# ardBeeQueen_12-pin_lcd.net
KiCad netlist of a schematic drawn in EAGLE
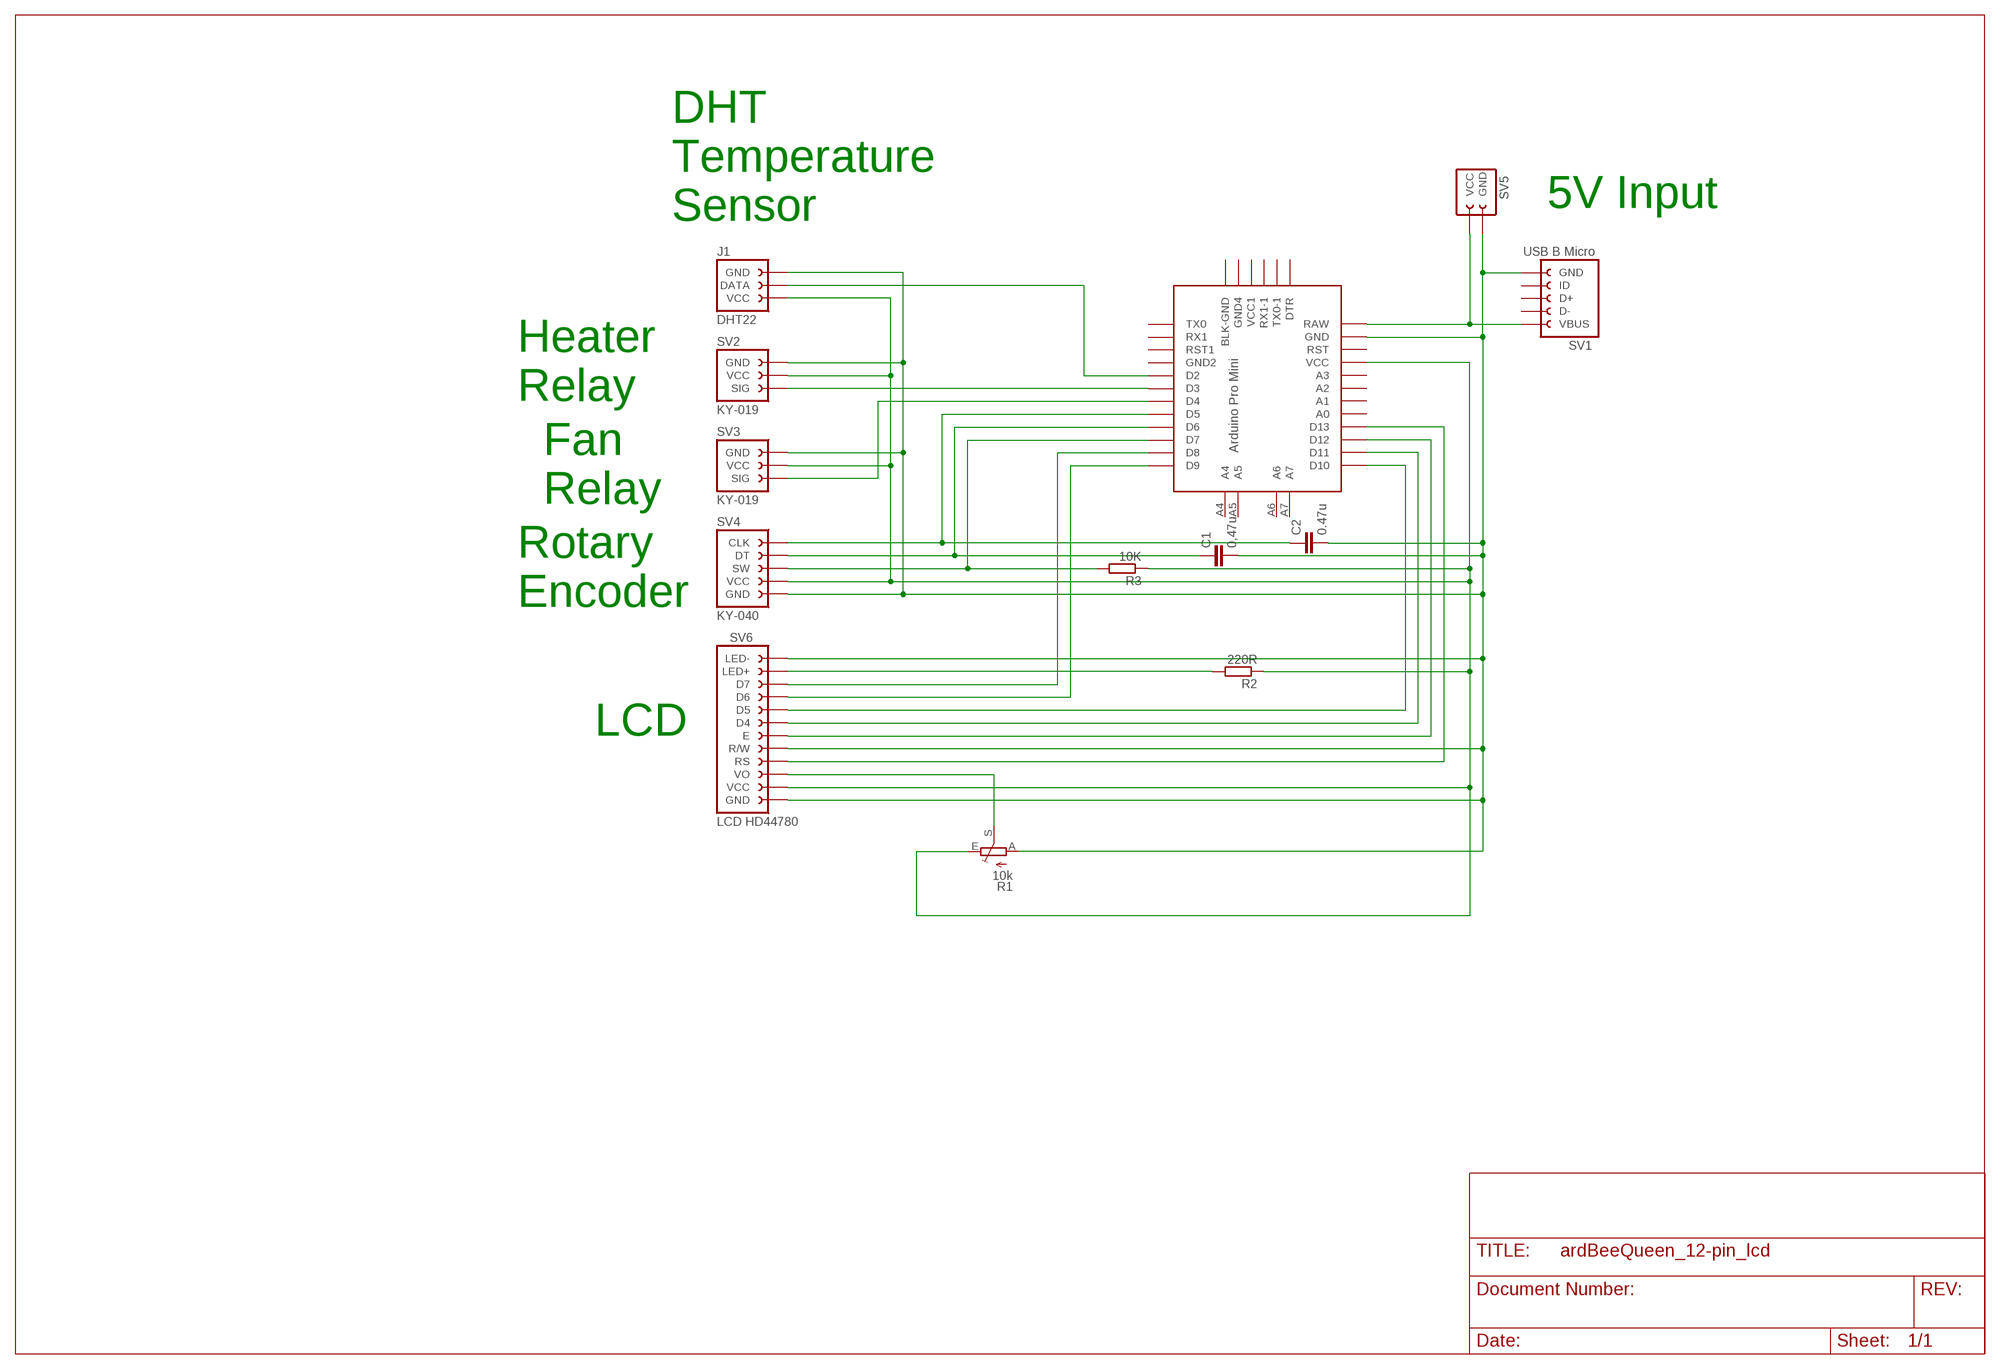
[diagram p0: schematic, sheet 1]

(export (version "E")
  (design (tool "Eeschema 10.0.6"))
  (components
    (comp (ref "C1")
      (value "0,47u")
      (footprint "eagle-import:C050-024X044")
      (libsource (lib "eagle-import") (part "C-EU050-024X044"))
    )
    (comp (ref "C2")
      (value "0.47u")
      (footprint "eagle-import:C050-024X044")
      (libsource (lib "eagle-import") (part "C-EU050-024X044"))
    )
    (comp (ref "J1")
      (value "DHT22_3-PIN_FEMALE_HEADER")
      (footprint "eagle-import:DHT22_3-PIN_FEMALE_HEADER")
      (libsource (lib "eagle-import") (part "DHT22_3-PIN_FEMALE_HEADER"))
    )
    (comp (ref "R1")
      (value "10k")
      (footprint "eagle-import:CA6V")
      (libsource (lib "eagle-import") (part "POTENTIOMETER_CA6VCA6V"))
    )
    (comp (ref "R2")
      (value "220R")
      (footprint "eagle-import:0207_10")
      (libsource (lib "eagle-import") (part "R-EU_0207/10"))
    )
    (comp (ref "R3")
      (value "10K")
      (footprint "eagle-import:0207_10")
      (libsource (lib "eagle-import") (part "R-EU_0207/10"))
    )
    (comp (ref "SV1")
      (value "MICROUSB_B_BREAKOUT_5-PIN_FEMALE_HEADERWITH_MOUNT_HOLES")
      (footprint "eagle-import:MICROUSB_B_BREAKOUT_5-PIN_FEMALE_HEADER_W_MOUNT_HOLES")
      (libsource (lib "eagle-import") (part "MICROUSB_B_BREAKOUT_5-PIN_FEMALE_HEADERWITH_MOUNT_HOLES"))
    )
    (comp (ref "SV2")
      (value "KY-019_3-PIN_FEMALE_HEADER")
      (footprint "eagle-import:KY-019_3-PIN_FEMALE_HEADER")
      (libsource (lib "eagle-import") (part "KY-019_3-PIN_FEMALE_HEADER"))
    )
    (comp (ref "SV3")
      (value "KY-019_3-PIN_FEMALE_HEADER")
      (footprint "eagle-import:KY-019_3-PIN_FEMALE_HEADER")
      (libsource (lib "eagle-import") (part "KY-019_3-PIN_FEMALE_HEADER"))
    )
    (comp (ref "SV4")
      (value "KY-040_5-PIN_FEMALE_HEADER")
      (footprint "eagle-import:KY-040_5-PIN_FEMALE_HEADER")
      (libsource (lib "eagle-import") (part "KY-040_5-PIN_FEMALE_HEADER"))
    )
    (comp (ref "SV5")
      (value "POWER_IN-2-PIN_FEMALE_HEADER")
      (footprint "eagle-import:POWER_IN-2-PIN_FEMALE_HEADER")
      (libsource (lib "eagle-import") (part "POWER_IN-2-PIN_FEMALE_HEADER"))
    )
    (comp (ref "SV6")
      (value "LCD-HD44780-12-PIN_FEMALE_HEADER")
      (footprint "eagle-import:LCD-HD44780-12-PIN_FEMALE_HEADER")
      (libsource (lib "eagle-import") (part "LCD-HD44780-12-PIN_FEMALE_HEADER"))
    )
    (comp (ref "U$1")
      (value "ARDUINO_PRO_MINI-2")
      (footprint "eagle-import:ARDUINO_PRO_MINI-2")
      (libsource (lib "eagle-import") (part "ARDUINO_PRO_MINI-2"))
    )
  )
  (nets
    (net (code "1") (name "Net-(C1-Pad1)") (class "Default")
      (node (ref "C1") (pin "1") (pinfunction "1_1") (pintype "passive"))
      (node (ref "SV4") (pin "DT") (pinfunction "DT_DT") (pintype "passive"))
      (node (ref "U$1") (pin "D6") (pinfunction "D6_D6") (pintype "bidirectional"))
    )
    (net (code "2") (name "Net-(C1-Pad2)") (class "Default")
      (node (ref "C1") (pin "2") (pinfunction "2_2") (pintype "passive"))
      (node (ref "C2") (pin "2") (pinfunction "2_2") (pintype "passive"))
      (node (ref "J1") (pin "GND") (pinfunction "GND_GND") (pintype "passive"))
      (node (ref "R1") (pin "A") (pinfunction "A_A") (pintype "passive"))
      (node (ref "SV1") (pin "GND") (pinfunction "GND_GND") (pintype "passive"))
      (node (ref "SV2") (pin "GND") (pinfunction "GND_GND") (pintype "passive"))
      (node (ref "SV3") (pin "GND") (pinfunction "GND_GND") (pintype "passive"))
      (node (ref "SV4") (pin "GND") (pinfunction "GND_GND") (pintype "passive"))
      (node (ref "SV5") (pin "GND") (pinfunction "GND_GND") (pintype "passive"))
      (node (ref "SV6") (pin "GND") (pinfunction "GND_GND") (pintype "passive"))
      (node (ref "SV6") (pin "LED-") (pinfunction "LED-_LED-") (pintype "passive"))
      (node (ref "SV6") (pin "R/W") (pinfunction "R/W_R/W") (pintype "passive"))
      (node (ref "U$1") (pin "GND") (pinfunction "GND_GND") (pintype "bidirectional"))
    )
    (net (code "3") (name "Net-(C2-Pad1)") (class "Default")
      (node (ref "C2") (pin "1") (pinfunction "1_1") (pintype "passive"))
      (node (ref "SV4") (pin "CLK") (pinfunction "CLK_CLK") (pintype "passive"))
      (node (ref "U$1") (pin "D5") (pinfunction "D5_D5") (pintype "bidirectional"))
    )
    (net (code "4") (name "Net-(J1-PadDATA)") (class "Default")
      (node (ref "J1") (pin "DATA") (pinfunction "DATA_DATA") (pintype "passive"))
      (node (ref "U$1") (pin "D2") (pinfunction "D2_D2") (pintype "bidirectional"))
    )
    (net (code "5") (name "Net-(J1-PadVCC)") (class "Default")
      (node (ref "J1") (pin "VCC") (pinfunction "VCC_VCC") (pintype "passive"))
      (node (ref "R1") (pin "E") (pinfunction "E_E") (pintype "passive"))
      (node (ref "R2") (pin "1") (pinfunction "1_1") (pintype "passive"))
      (node (ref "R3") (pin "1") (pinfunction "1_1") (pintype "passive"))
      (node (ref "SV2") (pin "VCC") (pinfunction "VCC_VCC") (pintype "passive"))
      (node (ref "SV3") (pin "VCC") (pinfunction "VCC_VCC") (pintype "passive"))
      (node (ref "SV4") (pin "VCC") (pinfunction "VCC_VCC") (pintype "passive"))
      (node (ref "SV6") (pin "VCC") (pinfunction "VCC_VCC") (pintype "passive"))
      (node (ref "U$1") (pin "VCC") (pinfunction "VCC_VCC") (pintype "bidirectional"))
    )
    (net (code "6") (name "Net-(R1-PadS)") (class "Default")
      (node (ref "R1") (pin "S") (pinfunction "S_S") (pintype "passive"))
      (node (ref "SV6") (pin "VO") (pinfunction "VO_VO") (pintype "passive"))
    )
    (net (code "7") (name "Net-(R2-Pad2)") (class "Default")
      (node (ref "R2") (pin "2") (pinfunction "2_2") (pintype "passive"))
      (node (ref "SV6") (pin "LED+") (pinfunction "LED+_LED+") (pintype "passive"))
    )
    (net (code "8") (name "Net-(R3-Pad2)") (class "Default")
      (node (ref "R3") (pin "2") (pinfunction "2_2") (pintype "passive"))
      (node (ref "SV4") (pin "SW") (pinfunction "SW_SW") (pintype "passive"))
      (node (ref "U$1") (pin "D7") (pinfunction "D7_D7") (pintype "bidirectional"))
    )
    (net (code "9") (name "Net-(SV1-PadVBUS)") (class "Default")
      (node (ref "SV1") (pin "VBUS") (pinfunction "VBUS_VBUS") (pintype "passive"))
      (node (ref "SV5") (pin "VCC") (pinfunction "VCC_VCC") (pintype "passive"))
      (node (ref "U$1") (pin "RAW") (pinfunction "RAW_RAW") (pintype "bidirectional"))
    )
    (net (code "10") (name "Net-(SV2-PadSIG)") (class "Default")
      (node (ref "SV2") (pin "SIG") (pinfunction "SIG_SIG") (pintype "passive"))
      (node (ref "U$1") (pin "D3") (pinfunction "D3_D3") (pintype "bidirectional"))
    )
    (net (code "11") (name "Net-(SV3-PadSIG)") (class "Default")
      (node (ref "SV3") (pin "SIG") (pinfunction "SIG_SIG") (pintype "passive"))
      (node (ref "U$1") (pin "D4") (pinfunction "D4_D4") (pintype "bidirectional"))
    )
    (net (code "12") (name "Net-(SV6-PadD4)") (class "Default")
      (node (ref "SV6") (pin "D4") (pinfunction "D4_D4") (pintype "passive"))
      (node (ref "U$1") (pin "D11") (pinfunction "D11_D11") (pintype "bidirectional"))
    )
    (net (code "13") (name "Net-(SV6-PadD5)") (class "Default")
      (node (ref "SV6") (pin "D5") (pinfunction "D5_D5") (pintype "passive"))
      (node (ref "U$1") (pin "D10") (pinfunction "D10_D10") (pintype "bidirectional"))
    )
    (net (code "14") (name "Net-(SV6-PadD6)") (class "Default")
      (node (ref "SV6") (pin "D6") (pinfunction "D6_D6") (pintype "passive"))
      (node (ref "U$1") (pin "D9") (pinfunction "D9_D9") (pintype "bidirectional"))
    )
    (net (code "15") (name "Net-(SV6-PadD7)") (class "Default")
      (node (ref "SV6") (pin "D7") (pinfunction "D7_D7") (pintype "passive"))
      (node (ref "U$1") (pin "D8") (pinfunction "D8_D8") (pintype "bidirectional"))
    )
    (net (code "16") (name "Net-(SV6-PadE)") (class "Default")
      (node (ref "SV6") (pin "E") (pinfunction "E_E") (pintype "passive"))
      (node (ref "U$1") (pin "D12") (pinfunction "D12_D12") (pintype "bidirectional"))
    )
    (net (code "17") (name "Net-(SV6-PadRS)") (class "Default")
      (node (ref "SV6") (pin "RS") (pinfunction "RS_RS") (pintype "passive"))
      (node (ref "U$1") (pin "D13") (pinfunction "D13_D13") (pintype "bidirectional"))
    )
    (net (code "18") (name "unconnected-(SV1-PadD+)") (class "Default")
      (node (ref "SV1") (pin "D+") (pinfunction "D+_D+") (pintype "passive"))
    )
    (net (code "19") (name "unconnected-(SV1-PadD-)") (class "Default")
      (node (ref "SV1") (pin "D-") (pinfunction "D-_D-") (pintype "passive"))
    )
    (net (code "20") (name "unconnected-(SV1-PadID)") (class "Default")
      (node (ref "SV1") (pin "ID") (pinfunction "ID_ID") (pintype "passive"))
    )
    (net (code "21") (name "unconnected-(U$1-GND2-PadGND1)") (class "Default")
      (node (ref "U$1") (pin "GND1") (pinfunction "GND2_GND1") (pintype "bidirectional"))
    )
    (net (code "22") (name "unconnected-(U$1-GND4-PadGND3)") (class "Default")
      (node (ref "U$1") (pin "GND3") (pinfunction "GND4_GND3") (pintype "bidirectional"))
    )
    (net (code "23") (name "unconnected-(U$1-PadA0)") (class "Default")
      (node (ref "U$1") (pin "A0") (pinfunction "A0_A0") (pintype "bidirectional"))
    )
    (net (code "24") (name "unconnected-(U$1-PadA1)") (class "Default")
      (node (ref "U$1") (pin "A1") (pinfunction "A1_A1") (pintype "bidirectional"))
    )
    (net (code "25") (name "unconnected-(U$1-PadA2)") (class "Default")
      (node (ref "U$1") (pin "A2") (pinfunction "A2_A2") (pintype "bidirectional"))
    )
    (net (code "26") (name "unconnected-(U$1-PadA3)") (class "Default")
      (node (ref "U$1") (pin "A3") (pinfunction "A3_A3") (pintype "bidirectional"))
    )
    (net (code "27") (name "unconnected-(U$1-PadA4)") (class "Default")
      (node (ref "U$1") (pin "A4") (pinfunction "A4_A4") (pintype "bidirectional"))
    )
    (net (code "28") (name "unconnected-(U$1-PadA5)") (class "Default")
      (node (ref "U$1") (pin "A5") (pinfunction "A5_A5") (pintype "bidirectional"))
    )
    (net (code "29") (name "unconnected-(U$1-PadA6)") (class "Default")
      (node (ref "U$1") (pin "A6") (pinfunction "A6_A6") (pintype "bidirectional"))
    )
    (net (code "30") (name "unconnected-(U$1-PadA7)") (class "Default")
      (node (ref "U$1") (pin "A7") (pinfunction "A7_A7") (pintype "bidirectional"))
    )
    (net (code "31") (name "unconnected-(U$1-PadBLK-GND)") (class "Default")
      (node (ref "U$1") (pin "BLK-GND") (pinfunction "BLK-GND_BLK-GND") (pintype "bidirectional"))
    )
    (net (code "32") (name "unconnected-(U$1-PadDTR)") (class "Default")
      (node (ref "U$1") (pin "DTR") (pinfunction "DTR_DTR") (pintype "bidirectional"))
    )
    (net (code "33") (name "unconnected-(U$1-PadRST)") (class "Default")
      (node (ref "U$1") (pin "RST") (pinfunction "RST_RST") (pintype "bidirectional"))
    )
    (net (code "34") (name "unconnected-(U$1-PadRST1)") (class "Default")
      (node (ref "U$1") (pin "RST1") (pinfunction "RST1_RST1") (pintype "bidirectional"))
    )
    (net (code "35") (name "unconnected-(U$1-PadRX1)") (class "Default")
      (node (ref "U$1") (pin "RX1") (pinfunction "RX1_RX1") (pintype "bidirectional"))
    )
    (net (code "36") (name "unconnected-(U$1-PadRX1-1)") (class "Default")
      (node (ref "U$1") (pin "RX1-1") (pinfunction "RX1-1_RX1-1") (pintype "bidirectional"))
    )
    (net (code "37") (name "unconnected-(U$1-PadTX0)") (class "Default")
      (node (ref "U$1") (pin "TX0") (pinfunction "TX0_TX0") (pintype "bidirectional"))
    )
    (net (code "38") (name "unconnected-(U$1-PadTX0-1)") (class "Default")
      (node (ref "U$1") (pin "TX0-1") (pinfunction "TX0-1_TX0-1") (pintype "bidirectional"))
    )
    (net (code "39") (name "unconnected-(U$1-PadVCC1)") (class "Default")
      (node (ref "U$1") (pin "VCC1") (pinfunction "VCC1_VCC1") (pintype "bidirectional"))
    )
  )
)
